# CY7C65211_Breakout.net
KiCad netlist of a schematic drawn in EAGLE
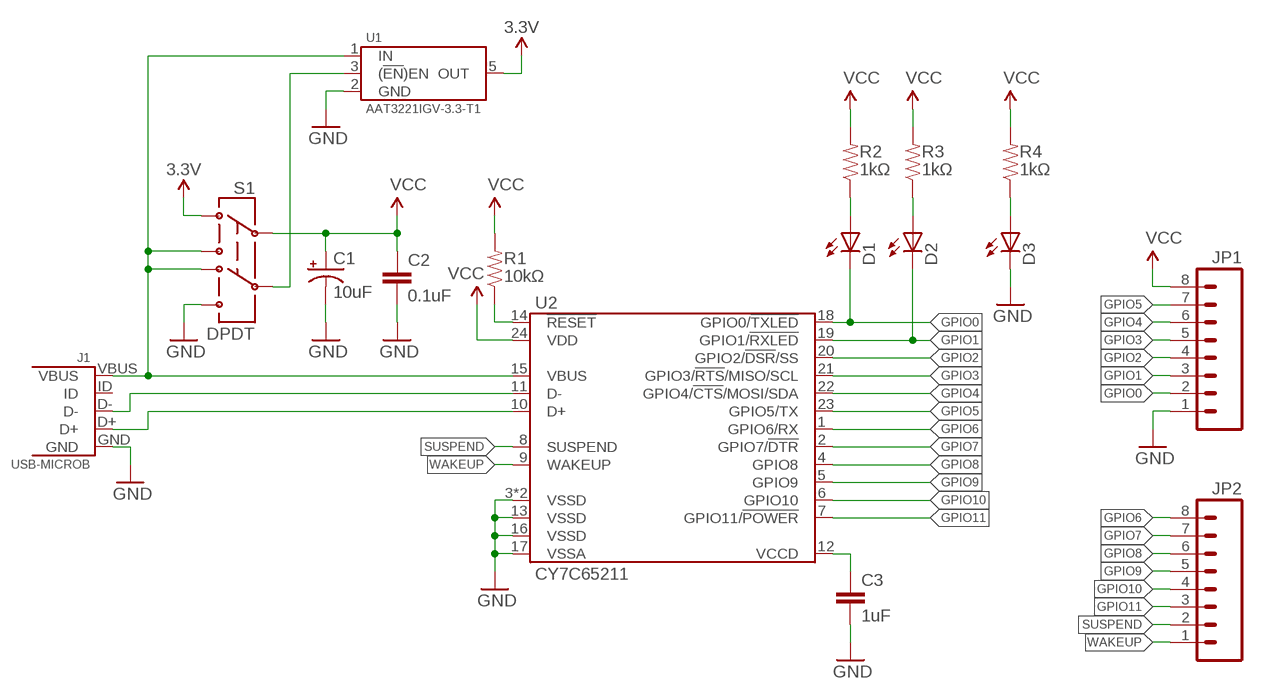
[diagram p0: schematic, sheet 1]

(export (version "E")
  (design (tool "Eeschema 10.0.6"))
  (components
    (comp (ref "C1")
      (value "10uF")
      (footprint "eagle-import:0805-CAP_POL")
      (libsource (lib "eagle-import") (part "CAP_POL0805"))
    )
    (comp (ref "C2")
      (value "0.1uF")
      (footprint "eagle-import:0402-CAP")
      (libsource (lib "eagle-import") (part "CAP-0402"))
    )
    (comp (ref "C3")
      (value "1uF")
      (footprint "eagle-import:0402-CAP")
      (libsource (lib "eagle-import") (part "CAP-0402"))
    )
    (comp (ref "D1")
      (value "LED0603")
      (footprint "eagle-import:LED-0603")
      (libsource (lib "eagle-import") (part "LED0603"))
    )
    (comp (ref "D2")
      (value "LED0603")
      (footprint "eagle-import:LED-0603")
      (libsource (lib "eagle-import") (part "LED0603"))
    )
    (comp (ref "D3")
      (value "LED0603")
      (footprint "eagle-import:LED-0603")
      (libsource (lib "eagle-import") (part "LED0603"))
    )
    (comp (ref "J1")
      (value "USB-MICROB")
      (footprint "eagle-import:USB-MICROB")
      (libsource (lib "eagle-import") (part "USB-MICROB"))
    )
    (comp (ref "JP1")
      (value "M081X08")
      (footprint "eagle-import:1X08")
      (libsource (lib "eagle-import") (part "M081X08"))
    )
    (comp (ref "JP2")
      (value "M081X08")
      (footprint "eagle-import:1X08")
      (libsource (lib "eagle-import") (part "M081X08"))
    )
    (comp (ref "R1")
      (value "10kΩ")
      (footprint "eagle-import:0402-RES")
      (libsource (lib "eagle-import") (part "RESISTOR"))
    )
    (comp (ref "R2")
      (value "1kΩ")
      (footprint "eagle-import:0402-RES")
      (libsource (lib "eagle-import") (part "RESISTOR"))
    )
    (comp (ref "R3")
      (value "1kΩ")
      (footprint "eagle-import:0402-RES")
      (libsource (lib "eagle-import") (part "RESISTOR"))
    )
    (comp (ref "R4")
      (value "1kΩ")
      (footprint "eagle-import:0402-RES")
      (libsource (lib "eagle-import") (part "RESISTOR"))
    )
    (comp (ref "S1")
      (value "DPDT")
      (footprint "eagle-import:AYZ0202")
      (libsource (lib "eagle-import") (part "SWITCH-DPDTAYZ0202"))
    )
    (comp (ref "U1")
      (value "AAT3221IGV-3.3-T1")
      (footprint "eagle-import:SOT23-5")
      (libsource (lib "eagle-import") (part "AAT3221IGV-3.3-T1"))
    )
    (comp (ref "U2")
      (value "CY7C65211")
      (footprint "eagle-import:QFN-24")
      (libsource (lib "eagle-import") (part "CY7C65211"))
    )
  )
  (nets
    (net (code "1") (name "3.3V") (class "Default")
      (node (ref "S1") (pin "1") (pinfunction "1_1") (pintype "bidirectional"))
      (node (ref "U1") (pin "5") (pinfunction "OUT_5") (pintype "bidirectional"))
    )
    (net (code "2") (name "GND") (class "Default")
      (node (ref "C1") (pin "C") (pinfunction "-_C") (pintype "passive"))
      (node (ref "C2") (pin "2") (pinfunction "2_2") (pintype "passive"))
      (node (ref "C3") (pin "2") (pinfunction "2_2") (pintype "passive"))
      (node (ref "D3") (pin "C") (pinfunction "C_C") (pintype "passive"))
      (node (ref "J1") (pin "GND") (pinfunction "GND_GND") (pintype "bidirectional"))
      (node (ref "JP1") (pin "1") (pinfunction "1_1") (pintype "passive"))
      (node (ref "S1") (pin "6") (pinfunction "6_6") (pintype "bidirectional"))
      (node (ref "U1") (pin "2") (pinfunction "GND_2") (pintype "bidirectional"))
      (node (ref "U2") (pin "13") (pinfunction "VSSD_13") (pintype "bidirectional"))
      (node (ref "U2") (pin "16") (pinfunction "VSSD_16") (pintype "bidirectional"))
      (node (ref "U2") (pin "17") (pinfunction "VSSA_17") (pintype "bidirectional"))
      (node (ref "U2") (pin "3") (pinfunction "VSSD_3") (pintype "bidirectional"))
      (node (ref "U2") (pin "EP") (pinfunction "VSSD_EP") (pintype "bidirectional"))
    )
    (net (code "3") (name "GPIO0") (class "Default")
      (node (ref "D1") (pin "C") (pinfunction "C_C") (pintype "passive"))
      (node (ref "JP1") (pin "2") (pinfunction "2_2") (pintype "passive"))
      (node (ref "U2") (pin "18") (pinfunction "GPIO0/~{TXLED}_18") (pintype "bidirectional"))
    )
    (net (code "4") (name "GPIO1") (class "Default")
      (node (ref "D2") (pin "C") (pinfunction "C_C") (pintype "passive"))
      (node (ref "JP1") (pin "3") (pinfunction "3_3") (pintype "passive"))
      (node (ref "U2") (pin "19") (pinfunction "GPIO1/~{RXLED}_19") (pintype "bidirectional"))
    )
    (net (code "5") (name "GPIO2") (class "Default")
      (node (ref "JP1") (pin "4") (pinfunction "4_4") (pintype "passive"))
      (node (ref "U2") (pin "20") (pinfunction "GPIO2/~{DSR}/SS_20") (pintype "bidirectional"))
    )
    (net (code "6") (name "GPIO3") (class "Default")
      (node (ref "JP1") (pin "5") (pinfunction "5_5") (pintype "passive"))
      (node (ref "U2") (pin "21") (pinfunction "GPIO3/~{RTS}/MISO/SCL_21") (pintype "bidirectional"))
    )
    (net (code "7") (name "GPIO4") (class "Default")
      (node (ref "JP1") (pin "6") (pinfunction "6_6") (pintype "passive"))
      (node (ref "U2") (pin "22") (pinfunction "GPIO4/~{CTS}/MOSI/SDA_22") (pintype "bidirectional"))
    )
    (net (code "8") (name "GPIO5") (class "Default")
      (node (ref "JP1") (pin "7") (pinfunction "7_7") (pintype "passive"))
      (node (ref "U2") (pin "23") (pinfunction "GPIO5/TX_23") (pintype "bidirectional"))
    )
    (net (code "9") (name "GPIO6") (class "Default")
      (node (ref "JP2") (pin "8") (pinfunction "8_8") (pintype "passive"))
      (node (ref "U2") (pin "1") (pinfunction "GPIO6/RX_1") (pintype "bidirectional"))
    )
    (net (code "10") (name "GPIO7") (class "Default")
      (node (ref "JP2") (pin "7") (pinfunction "7_7") (pintype "passive"))
      (node (ref "U2") (pin "2") (pinfunction "GPIO7/~{DTR}_2") (pintype "bidirectional"))
    )
    (net (code "11") (name "GPIO8") (class "Default")
      (node (ref "JP2") (pin "6") (pinfunction "6_6") (pintype "passive"))
      (node (ref "U2") (pin "4") (pinfunction "GPIO8_4") (pintype "bidirectional"))
    )
    (net (code "12") (name "GPIO9") (class "Default")
      (node (ref "JP2") (pin "5") (pinfunction "5_5") (pintype "passive"))
      (node (ref "U2") (pin "5") (pinfunction "GPIO9_5") (pintype "bidirectional"))
    )
    (net (code "13") (name "GPIO10") (class "Default")
      (node (ref "JP2") (pin "4") (pinfunction "4_4") (pintype "passive"))
      (node (ref "U2") (pin "6") (pinfunction "GPIO10_6") (pintype "bidirectional"))
    )
    (net (code "14") (name "GPIO11") (class "Default")
      (node (ref "JP2") (pin "3") (pinfunction "3_3") (pintype "passive"))
      (node (ref "U2") (pin "7") (pinfunction "GPIO11/~{POWER}_7") (pintype "bidirectional"))
    )
    (net (code "15") (name "Net-(D1-PadA)") (class "Default")
      (node (ref "D1") (pin "A") (pinfunction "A_A") (pintype "passive"))
      (node (ref "R2") (pin "1") (pinfunction "1_1") (pintype "passive"))
    )
    (net (code "16") (name "Net-(D2-PadA)") (class "Default")
      (node (ref "D2") (pin "A") (pinfunction "A_A") (pintype "passive"))
      (node (ref "R3") (pin "1") (pinfunction "1_1") (pintype "passive"))
    )
    (net (code "17") (name "Net-(D3-PadA)") (class "Default")
      (node (ref "D3") (pin "A") (pinfunction "A_A") (pintype "passive"))
      (node (ref "R4") (pin "1") (pinfunction "1_1") (pintype "passive"))
    )
    (net (code "18") (name "Net-(U1-(~{EN})EN)") (class "Default")
      (node (ref "S1") (pin "5") (pinfunction "5_5") (pintype "bidirectional"))
      (node (ref "U1") (pin "3") (pinfunction "(~{EN})EN_3") (pintype "bidirectional"))
    )
    (net (code "19") (name "Net-(U1-IN)") (class "Default")
      (node (ref "J1") (pin "VBUS") (pinfunction "VBUS_VBUS") (pintype "bidirectional"))
      (node (ref "S1") (pin "3") (pinfunction "3_3") (pintype "bidirectional"))
      (node (ref "S1") (pin "4") (pinfunction "4_4") (pintype "bidirectional"))
      (node (ref "U1") (pin "1") (pinfunction "IN_1") (pintype "bidirectional"))
      (node (ref "U2") (pin "15") (pinfunction "VBUS_15") (pintype "bidirectional"))
    )
    (net (code "20") (name "Net-(U2-D+)") (class "Default")
      (node (ref "J1") (pin "D+") (pinfunction "D+_D+") (pintype "bidirectional"))
      (node (ref "U2") (pin "10") (pinfunction "D+_10") (pintype "bidirectional"))
    )
    (net (code "21") (name "Net-(U2-D-)") (class "Default")
      (node (ref "J1") (pin "D-") (pinfunction "D-_D-") (pintype "bidirectional"))
      (node (ref "U2") (pin "11") (pinfunction "D-_11") (pintype "bidirectional"))
    )
    (net (code "22") (name "Net-(U2-VCCD)") (class "Default")
      (node (ref "C3") (pin "1") (pinfunction "1_1") (pintype "passive"))
      (node (ref "U2") (pin "12") (pinfunction "VCCD_12") (pintype "bidirectional"))
    )
    (net (code "23") (name "Net-(U2-~{RESET})") (class "Default")
      (node (ref "R1") (pin "1") (pinfunction "1_1") (pintype "passive"))
      (node (ref "U2") (pin "14") (pinfunction "~{RESET}_14") (pintype "bidirectional"))
    )
    (net (code "24") (name "SUSPEND") (class "Default")
      (node (ref "JP2") (pin "2") (pinfunction "2_2") (pintype "passive"))
      (node (ref "U2") (pin "8") (pinfunction "SUSPEND_8") (pintype "bidirectional"))
    )
    (net (code "25") (name "VCC") (class "Default")
      (node (ref "C1") (pin "A") (pinfunction "+_A") (pintype "passive"))
      (node (ref "C2") (pin "1") (pinfunction "1_1") (pintype "passive"))
      (node (ref "JP1") (pin "8") (pinfunction "8_8") (pintype "passive"))
      (node (ref "R1") (pin "2") (pinfunction "2_2") (pintype "passive"))
      (node (ref "R2") (pin "2") (pinfunction "2_2") (pintype "passive"))
      (node (ref "R3") (pin "2") (pinfunction "2_2") (pintype "passive"))
      (node (ref "R4") (pin "2") (pinfunction "2_2") (pintype "passive"))
      (node (ref "S1") (pin "2") (pinfunction "2_2") (pintype "bidirectional"))
      (node (ref "U2") (pin "24") (pinfunction "VDD_24") (pintype "bidirectional"))
    )
    (net (code "26") (name "WAKEUP") (class "Default")
      (node (ref "JP2") (pin "1") (pinfunction "1_1") (pintype "passive"))
      (node (ref "U2") (pin "9") (pinfunction "WAKEUP_9") (pintype "bidirectional"))
    )
    (net (code "27") (name "unconnected-(J1-PadID)") (class "Default")
      (node (ref "J1") (pin "ID") (pinfunction "ID_ID") (pintype "bidirectional"))
    )
  )
)
